# schematic_full.net
KiCad netlist of a schematic drawn in EAGLE
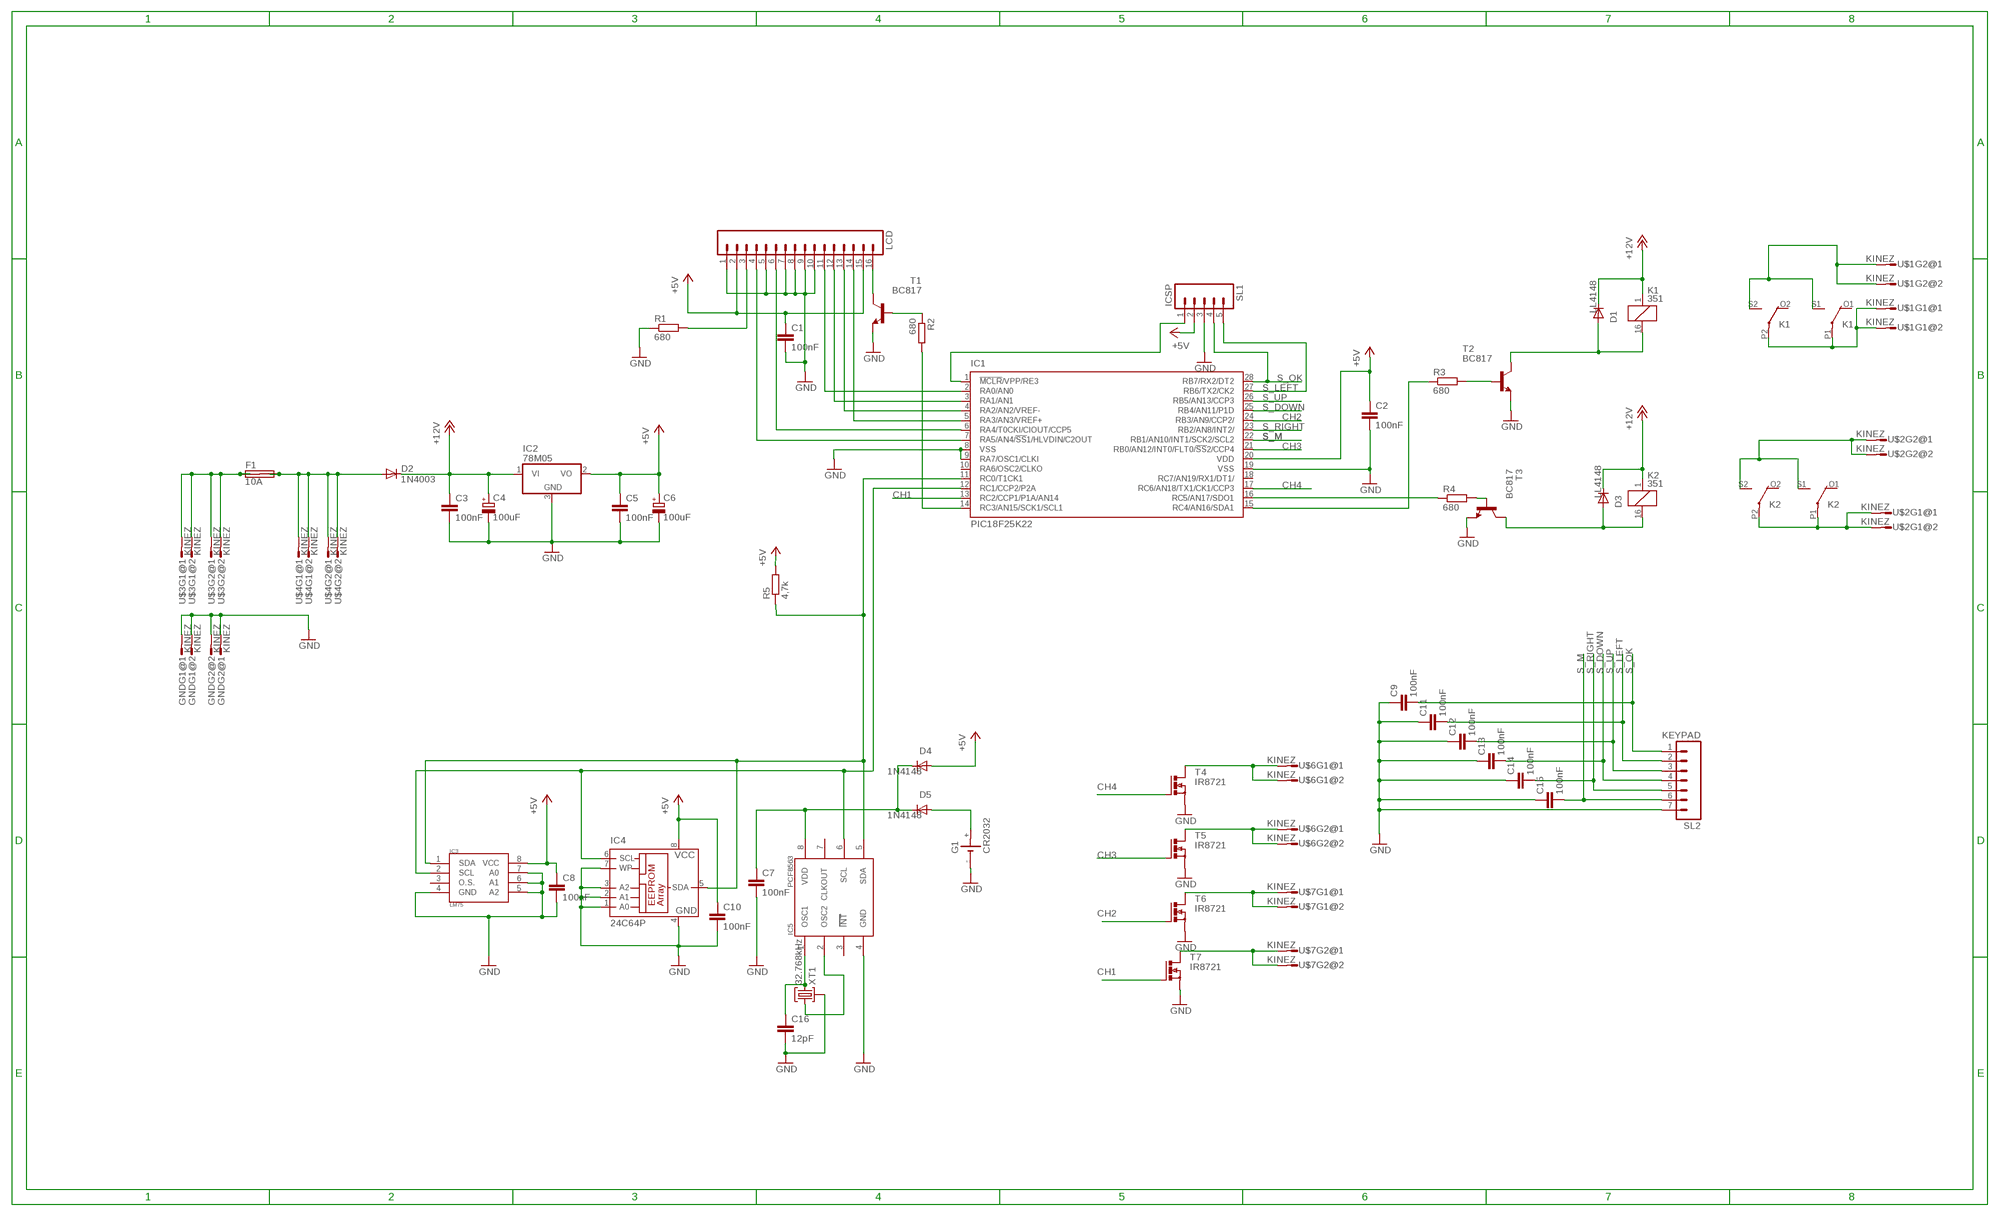
[diagram p0: schematic, sheet 1]

(export (version "E")
  (design (tool "Eeschema 10.0.6"))
  (components
    (comp (ref "C1")
      (value "100nF")
      (footprint "eagle-import:C0805K")
      (libsource (lib "eagle-import") (part "C-EUC0805K"))
    )
    (comp (ref "C2")
      (value "100nF")
      (footprint "eagle-import:C0805K")
      (libsource (lib "eagle-import") (part "C-EUC0805K"))
    )
    (comp (ref "C3")
      (value "100nF")
      (footprint "eagle-import:C0805K")
      (libsource (lib "eagle-import") (part "C-EUC0805K"))
    )
    (comp (ref "C4")
      (value "100uF")
      (footprint "eagle-import:E2,5-6E")
      (libsource (lib "eagle-import") (part "CPOL-EUE2,5-6E"))
    )
    (comp (ref "C5")
      (value "100nF")
      (footprint "eagle-import:C0805K")
      (libsource (lib "eagle-import") (part "C-EUC0805K"))
    )
    (comp (ref "C6")
      (value "100uF")
      (footprint "eagle-import:E2,5-6")
      (libsource (lib "eagle-import") (part "CPOL-EUE2.5-6"))
    )
    (comp (ref "C7")
      (value "100nF")
      (footprint "eagle-import:C0805K")
      (libsource (lib "eagle-import") (part "C-EUC0805K"))
    )
    (comp (ref "C8")
      (value "100nF")
      (footprint "eagle-import:C0805K")
      (libsource (lib "eagle-import") (part "C-EUC0805K"))
    )
    (comp (ref "C9")
      (value "100nF")
      (footprint "eagle-import:C0805K")
      (libsource (lib "eagle-import") (part "C-EUC0805K"))
    )
    (comp (ref "C10")
      (value "100nF")
      (footprint "eagle-import:C0805K")
      (libsource (lib "eagle-import") (part "C-EUC0805K"))
    )
    (comp (ref "C11")
      (value "100nF")
      (footprint "eagle-import:C0805K")
      (libsource (lib "eagle-import") (part "C-EUC0805K"))
    )
    (comp (ref "C12")
      (value "100nF")
      (footprint "eagle-import:C0805K")
      (libsource (lib "eagle-import") (part "C-EUC0805K"))
    )
    (comp (ref "C13")
      (value "100nF")
      (footprint "eagle-import:C0805K")
      (libsource (lib "eagle-import") (part "C-EUC0805K"))
    )
    (comp (ref "C14")
      (value "100nF")
      (footprint "eagle-import:C0805K")
      (libsource (lib "eagle-import") (part "C-EUC0805K"))
    )
    (comp (ref "C15")
      (value "100nF")
      (footprint "eagle-import:C0805K")
      (libsource (lib "eagle-import") (part "C-EUC0805K"))
    )
    (comp (ref "C16")
      (value "12pF")
      (footprint "eagle-import:C0805K")
      (libsource (lib "eagle-import") (part "C-EUC0805K"))
    )
    (comp (ref "D1")
      (value "LL4148")
      (footprint "eagle-import:DO214BA")
      (libsource (lib "eagle-import") (part "DIODE-DO214BA"))
    )
    (comp (ref "D2")
      (value "1N4003")
      (footprint "eagle-import:DO41-10")
      (libsource (lib "eagle-import") (part "1N4933"))
    )
    (comp (ref "D3")
      (value "LL4148")
      (footprint "eagle-import:DO214BA")
      (libsource (lib "eagle-import") (part "DIODE-DO214BA"))
    )
    (comp (ref "D4")
      (value "1N4148")
      (footprint "eagle-import:DO214BA")
      (libsource (lib "eagle-import") (part "DIODE-DO214BA"))
    )
    (comp (ref "D5")
      (value "1N4148")
      (footprint "eagle-import:DO214BA")
      (libsource (lib "eagle-import") (part "DIODE-DO214BA"))
    )
    (comp (ref "F1")
      (value "10A")
      (footprint "eagle-import:SHK20L")
      (libsource (lib "eagle-import") (part "SHK20L"))
    )
    (comp (ref "G1")
      (value "CR2032")
      (footprint "eagle-import:CR2032")
      (libsource (lib "eagle-import") (part "CR2032"))
    )
    (comp (ref "GND")
      (value "KINEZ")
      (footprint "eagle-import:KINEZ")
      (libsource (lib "eagle-import") (part "KINEZ"))
    )
    (comp (ref "IC1")
      (value "PIC18F25K22")
      (footprint "eagle-import:SSOP28")
      (libsource (lib "eagle-import") (part "PIC18F25K22/SS-E"))
    )
    (comp (ref "IC2")
      (value "78M05")
      (footprint "eagle-import:TO252")
      (libsource (lib "eagle-import") (part "78DT05"))
    )
    (comp (ref "IC3")
      (value "LM75")
      (footprint "eagle-import:SO08")
      (libsource (lib "eagle-import") (part "LM75"))
    )
    (comp (ref "IC4")
      (value "24C64P")
      (footprint "eagle-import:DIL8")
      (libsource (lib "eagle-import") (part "24PC64"))
    )
    (comp (ref "IC5")
      (value "PCF8563")
      (footprint "eagle-import:SO08")
      (libsource (lib "eagle-import") (part "PCF8563"))
    )
    (comp (ref "K1")
      (value "351")
      (footprint "eagle-import:351")
      (libsource (lib "eagle-import") (part "351"))
    )
    (comp (ref "K2")
      (value "351")
      (footprint "eagle-import:351")
      (libsource (lib "eagle-import") (part "351"))
    )
    (comp (ref "LCD")
      (value "M16")
      (footprint "eagle-import:16P")
      (libsource (lib "eagle-import") (part "M16"))
    )
    (comp (ref "R1")
      (value "680")
      (footprint "eagle-import:M0805")
      (libsource (lib "eagle-import") (part "R-EU_M0805"))
    )
    (comp (ref "R2")
      (value "680")
      (footprint "eagle-import:M0805")
      (libsource (lib "eagle-import") (part "R-EU_M0805"))
    )
    (comp (ref "R3")
      (value "680")
      (footprint "eagle-import:M0805")
      (libsource (lib "eagle-import") (part "R-EU_M0805"))
    )
    (comp (ref "R4")
      (value "680")
      (footprint "eagle-import:M0805")
      (libsource (lib "eagle-import") (part "R-EU_M0805"))
    )
    (comp (ref "R5")
      (value "4,7k")
      (footprint "eagle-import:M0805")
      (libsource (lib "eagle-import") (part "R-EU_M0805"))
    )
    (comp (ref "SL1")
      (value "ICSP")
      (footprint "eagle-import:05P")
      (libsource (lib "eagle-import") (part "M05"))
    )
    (comp (ref "SL2")
      (value "KEYPAD")
      (footprint "eagle-import:07PA")
      (libsource (lib "eagle-import") (part "MA07"))
    )
    (comp (ref "T1")
      (value "BC817")
      (footprint "eagle-import:SOT23-BEC")
      (libsource (lib "eagle-import") (part "BC817SMD-40"))
    )
    (comp (ref "T2")
      (value "BC817")
      (footprint "eagle-import:SOT23-BEC")
      (libsource (lib "eagle-import") (part "BC817SMD-40"))
    )
    (comp (ref "T3")
      (value "BC817")
      (footprint "eagle-import:SOT23-BEC")
      (libsource (lib "eagle-import") (part "BC817SMD-40"))
    )
    (comp (ref "T4")
      (value "IR8721")
      (footprint "eagle-import:TO252")
      (libsource (lib "eagle-import") (part "IRLR120N"))
    )
    (comp (ref "T5")
      (value "IR8721")
      (footprint "eagle-import:TO252")
      (libsource (lib "eagle-import") (part "IRLR120N"))
    )
    (comp (ref "T6")
      (value "IR8721")
      (footprint "eagle-import:TO252")
      (libsource (lib "eagle-import") (part "IRLR120N"))
    )
    (comp (ref "T7")
      (value "IR8721")
      (footprint "eagle-import:TO252")
      (libsource (lib "eagle-import") (part "IRLR120N"))
    )
    (comp (ref "U$1")
      (value "KINEZ")
      (footprint "eagle-import:KINEZ")
      (libsource (lib "eagle-import") (part "KINEZ"))
    )
    (comp (ref "U$2")
      (value "KINEZ")
      (footprint "eagle-import:KINEZ")
      (libsource (lib "eagle-import") (part "KINEZ"))
    )
    (comp (ref "U$3")
      (value "KINEZ")
      (footprint "eagle-import:KINEZ")
      (libsource (lib "eagle-import") (part "KINEZ"))
    )
    (comp (ref "U$4")
      (value "KINEZ")
      (footprint "eagle-import:KINEZ")
      (libsource (lib "eagle-import") (part "KINEZ"))
    )
    (comp (ref "U$6")
      (value "KINEZ")
      (footprint "eagle-import:KINEZ")
      (libsource (lib "eagle-import") (part "KINEZ"))
    )
    (comp (ref "U$7")
      (value "KINEZ")
      (footprint "eagle-import:KINEZ")
      (libsource (lib "eagle-import") (part "KINEZ"))
    )
    (comp (ref "XT1")
      (value "32.768kHz")
      (footprint "eagle-import:XTMINI")
      (libsource (lib "eagle-import") (part "XTMINI"))
    )
  )
  (nets
    (net (code "1") (name "+5V") (class "Default")
      (node (ref "C1") (pin "1") (pinfunction "1_1") (pintype "passive"))
      (node (ref "C10") (pin "1") (pinfunction "1_1") (pintype "passive"))
      (node (ref "C2") (pin "1") (pinfunction "1_1") (pintype "passive"))
      (node (ref "C5") (pin "1") (pinfunction "1_1") (pintype "passive"))
      (node (ref "C6") (pin "+") (pinfunction "+_+") (pintype "passive"))
      (node (ref "C8") (pin "1") (pinfunction "1_1") (pintype "passive"))
      (node (ref "D4") (pin "A") (pinfunction "A_A") (pintype "passive"))
      (node (ref "IC1") (pin "20") (pinfunction "VDD_20") (pintype "power_in"))
      (node (ref "IC2") (pin "2") (pinfunction "VO_2") (pintype "passive"))
      (node (ref "IC3") (pin "8") (pinfunction "VCC_8") (pintype "bidirectional"))
      (node (ref "IC4") (pin "8") (pinfunction "VCC_8") (pintype "power_in"))
      (node (ref "LCD") (pin "15") (pinfunction "15_15") (pintype "passive"))
      (node (ref "LCD") (pin "2") (pinfunction "2_2") (pintype "passive"))
      (node (ref "R5") (pin "2") (pinfunction "2_2") (pintype "passive"))
      (node (ref "SL1") (pin "2") (pinfunction "2_2") (pintype "passive"))
    )
    (net (code "2") (name "+12V") (class "Default")
      (node (ref "C3") (pin "1") (pinfunction "1_1") (pintype "passive"))
      (node (ref "C4") (pin "+") (pinfunction "+_+") (pintype "passive"))
      (node (ref "D1") (pin "C") (pinfunction "C_C") (pintype "passive"))
      (node (ref "D2") (pin "C") (pinfunction "C_C") (pintype "passive"))
      (node (ref "D3") (pin "C") (pinfunction "C_C") (pintype "passive"))
      (node (ref "IC2") (pin "1") (pinfunction "VI_1") (pintype "input"))
      (node (ref "K1") (pin "1") (pinfunction "1_1") (pintype "passive"))
      (node (ref "K2") (pin "1") (pinfunction "1_1") (pintype "passive"))
    )
    (net (code "3") (name "/CH1") (class "Default")
      (node (ref "IC1") (pin "13") (pinfunction "RC2/CCP1/P1A/AN14_13") (pintype "bidirectional"))
      (node (ref "T7") (pin "1") (pinfunction "G_1") (pintype "passive"))
    )
    (net (code "4") (name "/CH2") (class "Default")
      (node (ref "IC1") (pin "24") (pinfunction "RB3/AN9/CCP2/_24") (pintype "bidirectional"))
      (node (ref "T6") (pin "1") (pinfunction "G_1") (pintype "passive"))
    )
    (net (code "5") (name "/CH3") (class "Default")
      (node (ref "IC1") (pin "21") (pinfunction "RB0/AN12/INT0/FLT0/~{SS}2/CCP4_21") (pintype "bidirectional"))
      (node (ref "T5") (pin "1") (pinfunction "G_1") (pintype "passive"))
    )
    (net (code "6") (name "/CH4") (class "Default")
      (node (ref "IC1") (pin "17") (pinfunction "RC6/AN18/TX1/CK1/CCP3_17") (pintype "bidirectional"))
      (node (ref "T4") (pin "1") (pinfunction "G_1") (pintype "passive"))
    )
    (net (code "7") (name "/S_DOWN") (class "Default")
      (node (ref "C13") (pin "2") (pinfunction "2_2") (pintype "passive"))
      (node (ref "IC1") (pin "25") (pinfunction "RB4/AN11/P1D_25") (pintype "bidirectional"))
      (node (ref "SL2") (pin "4") (pinfunction "4_4") (pintype "passive"))
    )
    (net (code "8") (name "/S_LEFT") (class "Default")
      (node (ref "C11") (pin "2") (pinfunction "2_2") (pintype "passive"))
      (node (ref "IC1") (pin "27") (pinfunction "RB6/TX2/CK2_27") (pintype "bidirectional"))
      (node (ref "SL1") (pin "5") (pinfunction "5_5") (pintype "passive"))
      (node (ref "SL2") (pin "2") (pinfunction "2_2") (pintype "passive"))
    )
    (net (code "9") (name "/S_M") (class "Default")
      (node (ref "C15") (pin "2") (pinfunction "2_2") (pintype "passive"))
      (node (ref "IC1") (pin "22") (pinfunction "RB1/AN10/INT1/SCK2/SCL2_22") (pintype "bidirectional"))
      (node (ref "SL2") (pin "6") (pinfunction "6_6") (pintype "passive"))
    )
    (net (code "10") (name "/S_OK") (class "Default")
      (node (ref "C9") (pin "2") (pinfunction "2_2") (pintype "passive"))
      (node (ref "IC1") (pin "28") (pinfunction "RB7/RX2/DT2_28") (pintype "bidirectional"))
      (node (ref "SL1") (pin "4") (pinfunction "4_4") (pintype "passive"))
      (node (ref "SL2") (pin "1") (pinfunction "1_1") (pintype "passive"))
    )
    (net (code "11") (name "/S_RIGHT") (class "Default")
      (node (ref "C14") (pin "2") (pinfunction "2_2") (pintype "passive"))
      (node (ref "IC1") (pin "23") (pinfunction "RB2/AN8/INT2/_23") (pintype "bidirectional"))
      (node (ref "SL2") (pin "5") (pinfunction "5_5") (pintype "passive"))
    )
    (net (code "12") (name "/S_UP") (class "Default")
      (node (ref "C12") (pin "2") (pinfunction "2_2") (pintype "passive"))
      (node (ref "IC1") (pin "26") (pinfunction "RB5/AN13/CCP3_26") (pintype "bidirectional"))
      (node (ref "SL2") (pin "3") (pinfunction "3_3") (pintype "passive"))
    )
    (net (code "13") (name "GND") (class "Default")
      (node (ref "C1") (pin "2") (pinfunction "2_2") (pintype "passive"))
      (node (ref "C10") (pin "2") (pinfunction "2_2") (pintype "passive"))
      (node (ref "C11") (pin "1") (pinfunction "1_1") (pintype "passive"))
      (node (ref "C12") (pin "1") (pinfunction "1_1") (pintype "passive"))
      (node (ref "C13") (pin "1") (pinfunction "1_1") (pintype "passive"))
      (node (ref "C14") (pin "1") (pinfunction "1_1") (pintype "passive"))
      (node (ref "C15") (pin "1") (pinfunction "1_1") (pintype "passive"))
      (node (ref "C16") (pin "2") (pinfunction "2_2") (pintype "passive"))
      (node (ref "C2") (pin "2") (pinfunction "2_2") (pintype "passive"))
      (node (ref "C3") (pin "2") (pinfunction "2_2") (pintype "passive"))
      (node (ref "C4") (pin "-") (pinfunction "-_-") (pintype "passive"))
      (node (ref "C5") (pin "2") (pinfunction "2_2") (pintype "passive"))
      (node (ref "C6") (pin "-") (pinfunction "-_-") (pintype "passive"))
      (node (ref "C7") (pin "2") (pinfunction "2_2") (pintype "passive"))
      (node (ref "C8") (pin "2") (pinfunction "2_2") (pintype "passive"))
      (node (ref "C9") (pin "1") (pinfunction "1_1") (pintype "passive"))
      (node (ref "G1") (pin "-") (pinfunction "-_-") (pintype "passive"))
      (node (ref "GND") (pin "1") (pinfunction "S_1") (pintype "passive"))
      (node (ref "GND") (pin "2") (pinfunction "S_2") (pintype "passive"))
      (node (ref "GND") (pin "3") (pinfunction "S_3") (pintype "passive"))
      (node (ref "GND") (pin "4") (pinfunction "S_4") (pintype "passive"))
      (node (ref "IC1") (pin "19") (pinfunction "VSS_19") (pintype "power_in"))
      (node (ref "IC1") (pin "8") (pinfunction "VSS_8") (pintype "power_in"))
      (node (ref "IC1") (pin "9") (pinfunction "RA7/OSC1/CLKI_9") (pintype "input"))
      (node (ref "IC2") (pin "3") (pinfunction "GND_3") (pintype "passive"))
      (node (ref "IC3") (pin "4") (pinfunction "GND_4") (pintype "bidirectional"))
      (node (ref "IC3") (pin "5") (pinfunction "A2_5") (pintype "bidirectional"))
      (node (ref "IC3") (pin "6") (pinfunction "A1_6") (pintype "bidirectional"))
      (node (ref "IC3") (pin "7") (pinfunction "A0_7") (pintype "bidirectional"))
      (node (ref "IC4") (pin "1") (pinfunction "A0_1") (pintype "input"))
      (node (ref "IC4") (pin "2") (pinfunction "A1_2") (pintype "input"))
      (node (ref "IC4") (pin "3") (pinfunction "A2_3") (pintype "input"))
      (node (ref "IC4") (pin "4") (pinfunction "GND_4") (pintype "power_in"))
      (node (ref "IC4") (pin "7") (pinfunction "WP_7") (pintype "input"))
      (node (ref "IC5") (pin "4") (pinfunction "GND_4") (pintype "bidirectional"))
      (node (ref "LCD") (pin "1") (pinfunction "1_1") (pintype "passive"))
      (node (ref "LCD") (pin "10") (pinfunction "10_10") (pintype "passive"))
      (node (ref "LCD") (pin "5") (pinfunction "5_5") (pintype "passive"))
      (node (ref "LCD") (pin "7") (pinfunction "7_7") (pintype "passive"))
      (node (ref "LCD") (pin "8") (pinfunction "8_8") (pintype "passive"))
      (node (ref "LCD") (pin "9") (pinfunction "9_9") (pintype "passive"))
      (node (ref "R1") (pin "1") (pinfunction "1_1") (pintype "passive"))
      (node (ref "SL1") (pin "3") (pinfunction "3_3") (pintype "passive"))
      (node (ref "SL2") (pin "7") (pinfunction "7_7") (pintype "passive"))
      (node (ref "T1") (pin "E") (pinfunction "E_E") (pintype "passive"))
      (node (ref "T2") (pin "E") (pinfunction "E_E") (pintype "passive"))
      (node (ref "T3") (pin "E") (pinfunction "E_E") (pintype "passive"))
      (node (ref "T4") (pin "3") (pinfunction "S_3") (pintype "passive"))
      (node (ref "T5") (pin "3") (pinfunction "S_3") (pintype "passive"))
      (node (ref "T6") (pin "3") (pinfunction "S_3") (pintype "passive"))
      (node (ref "T7") (pin "3") (pinfunction "S_3") (pintype "passive"))
      (node (ref "XT1") (pin "P$3") (pinfunction "3_P$3") (pintype "passive"))
    )
    (net (code "14") (name "Net-(D5-PadA)") (class "Default")
      (node (ref "D5") (pin "A") (pinfunction "A_A") (pintype "passive"))
      (node (ref "G1") (pin "+") (pinfunction "+_+") (pintype "passive"))
    )
    (net (code "15") (name "Net-(IC1-RA0{slash}AN0)") (class "Default")
      (node (ref "IC1") (pin "2") (pinfunction "RA0/AN0_2") (pintype "bidirectional"))
      (node (ref "LCD") (pin "11") (pinfunction "11_11") (pintype "passive"))
    )
    (net (code "16") (name "Net-(IC1-RA1{slash}AN1)") (class "Default")
      (node (ref "IC1") (pin "3") (pinfunction "RA1/AN1_3") (pintype "bidirectional"))
      (node (ref "LCD") (pin "12") (pinfunction "12_12") (pintype "passive"))
    )
    (net (code "17") (name "Net-(IC1-RA2{slash}AN2{slash}VREF-)") (class "Default")
      (node (ref "IC1") (pin "4") (pinfunction "RA2/AN2/VREF-_4") (pintype "bidirectional"))
      (node (ref "LCD") (pin "13") (pinfunction "13_13") (pintype "passive"))
    )
    (net (code "18") (name "Net-(IC1-RA3{slash}AN3{slash}VREF+)") (class "Default")
      (node (ref "IC1") (pin "5") (pinfunction "RA3/AN3/VREF+_5") (pintype "bidirectional"))
      (node (ref "LCD") (pin "14") (pinfunction "14_14") (pintype "passive"))
    )
    (net (code "19") (name "Net-(IC1-RA4{slash}T0CKI{slash}CIOUT{slash}CCP5)") (class "Default")
      (node (ref "IC1") (pin "6") (pinfunction "RA4/T0CKI/CIOUT/CCP5_6") (pintype "bidirectional"))
      (node (ref "LCD") (pin "6") (pinfunction "6_6") (pintype "passive"))
    )
    (net (code "20") (name "Net-(IC1-RA5{slash}AN4{slash}~{SS}1{slash}HLVDIN{slash}C2OUT)") (class "Default")
      (node (ref "IC1") (pin "7") (pinfunction "RA5/AN4/~{SS}1/HLVDIN/C2OUT_7") (pintype "bidirectional"))
      (node (ref "LCD") (pin "4") (pinfunction "4_4") (pintype "passive"))
    )
    (net (code "21") (name "Net-(IC1-RC0{slash}T1CK1)") (class "Default")
      (node (ref "IC1") (pin "11") (pinfunction "RC0/T1CK1_11") (pintype "bidirectional"))
      (node (ref "IC3") (pin "1") (pinfunction "SDA_1") (pintype "bidirectional"))
      (node (ref "IC4") (pin "5") (pinfunction "SDA_5") (pintype "bidirectional"))
      (node (ref "IC5") (pin "5") (pinfunction "SDA_5") (pintype "bidirectional"))
      (node (ref "R5") (pin "1") (pinfunction "1_1") (pintype "passive"))
    )
    (net (code "22") (name "Net-(IC1-RC1{slash}CCP2{slash}P2A)") (class "Default")
      (node (ref "IC1") (pin "12") (pinfunction "RC1/CCP2/P2A_12") (pintype "bidirectional"))
      (node (ref "IC3") (pin "2") (pinfunction "SCL_2") (pintype "bidirectional"))
      (node (ref "IC4") (pin "6") (pinfunction "SCL_6") (pintype "input"))
      (node (ref "IC5") (pin "6") (pinfunction "SCL_6") (pintype "bidirectional"))
    )
    (net (code "23") (name "Net-(IC1-RC3{slash}AN15{slash}SCK1{slash}SCL1)") (class "Default")
      (node (ref "IC1") (pin "14") (pinfunction "RC3/AN15/SCK1/SCL1_14") (pintype "bidirectional"))
      (node (ref "R2") (pin "2") (pinfunction "2_2") (pintype "passive"))
    )
    (net (code "24") (name "Net-(IC1-RC4{slash}AN16{slash}SDA1)") (class "Default")
      (node (ref "IC1") (pin "15") (pinfunction "RC4/AN16/SDA1_15") (pintype "bidirectional"))
      (node (ref "R3") (pin "1") (pinfunction "1_1") (pintype "passive"))
    )
    (net (code "25") (name "Net-(IC1-RC5{slash}AN17{slash}SDO1)") (class "Default")
      (node (ref "IC1") (pin "16") (pinfunction "RC5/AN17/SDO1_16") (pintype "bidirectional"))
      (node (ref "R4") (pin "1") (pinfunction "1_1") (pintype "passive"))
    )
    (net (code "26") (name "Net-(IC1-~{MCLR}{slash}VPP{slash}RE3)") (class "Default")
      (node (ref "IC1") (pin "1") (pinfunction "~{MCLR}/VPP/RE3_1") (pintype "input"))
      (node (ref "SL1") (pin "1") (pinfunction "1_1") (pintype "passive"))
    )
    (net (code "27") (name "Net-(IC5-OSC1)") (class "Default")
      (node (ref "C16") (pin "1") (pinfunction "1_1") (pintype "passive"))
      (node (ref "IC5") (pin "1") (pinfunction "OSC1_1") (pintype "bidirectional"))
      (node (ref "XT1") (pin "P$2") (pinfunction "2_P$2") (pintype "passive"))
    )
    (net (code "28") (name "Net-(IC5-OSC2)") (class "Default")
      (node (ref "IC5") (pin "2") (pinfunction "OSC2_2") (pintype "bidirectional"))
      (node (ref "XT1") (pin "P$1") (pinfunction "1_P$1") (pintype "passive"))
    )
    (net (code "29") (name "Net-(IC5-VDD)") (class "Default")
      (node (ref "C7") (pin "1") (pinfunction "1_1") (pintype "passive"))
      (node (ref "D4") (pin "C") (pinfunction "C_C") (pintype "passive"))
      (node (ref "D5") (pin "C") (pinfunction "C_C") (pintype "passive"))
      (node (ref "IC5") (pin "8") (pinfunction "VDD_8") (pintype "bidirectional"))
    )
    (net (code "30") (name "Net-(K1A-2)") (class "Default")
      (node (ref "D1") (pin "A") (pinfunction "A_A") (pintype "passive"))
      (node (ref "K1") (pin "16") (pinfunction "2_16") (pintype "passive"))
      (node (ref "T2") (pin "C") (pinfunction "C_C") (pintype "passive"))
    )
    (net (code "31") (name "Net-(K1B-P)") (class "Default")
      (node (ref "K1") (pin "P1") (pinfunction "P_P1") (pintype "passive"))
      (node (ref "K1") (pin "P2") (pinfunction "P_P2") (pintype "passive"))
      (node (ref "U$1") (pin "1") (pinfunction "S_1") (pintype "passive"))
      (node (ref "U$1") (pin "2") (pinfunction "S_2") (pintype "passive"))
    )
    (net (code "32") (name "Net-(K1B-S)") (class "Default")
      (node (ref "K1") (pin "S1") (pinfunction "S_S1") (pintype "passive"))
      (node (ref "K1") (pin "S2") (pinfunction "S_S2") (pintype "passive"))
      (node (ref "U$1") (pin "3") (pinfunction "S_3") (pintype "passive"))
      (node (ref "U$1") (pin "4") (pinfunction "S_4") (pintype "passive"))
    )
    (net (code "33") (name "Net-(K2A-2)") (class "Default")
      (node (ref "D3") (pin "A") (pinfunction "A_A") (pintype "passive"))
      (node (ref "K2") (pin "16") (pinfunction "2_16") (pintype "passive"))
      (node (ref "T3") (pin "C") (pinfunction "C_C") (pintype "passive"))
    )
    (net (code "34") (name "Net-(K2B-P)") (class "Default")
      (node (ref "K2") (pin "P1") (pinfunction "P_P1") (pintype "passive"))
      (node (ref "K2") (pin "P2") (pinfunction "P_P2") (pintype "passive"))
      (node (ref "U$2") (pin "1") (pinfunction "S_1") (pintype "passive"))
      (node (ref "U$2") (pin "2") (pinfunction "S_2") (pintype "passive"))
    )
    (net (code "35") (name "Net-(K2B-S)") (class "Default")
      (node (ref "K2") (pin "S1") (pinfunction "S_S1") (pintype "passive"))
      (node (ref "K2") (pin "S2") (pinfunction "S_S2") (pintype "passive"))
      (node (ref "U$2") (pin "3") (pinfunction "S_3") (pintype "passive"))
      (node (ref "U$2") (pin "4") (pinfunction "S_4") (pintype "passive"))
    )
    (net (code "36") (name "Net-(LCD-Pad3)") (class "Default")
      (node (ref "LCD") (pin "3") (pinfunction "3_3") (pintype "passive"))
      (node (ref "R1") (pin "2") (pinfunction "2_2") (pintype "passive"))
    )
    (net (code "37") (name "Net-(LCD-Pad16)") (class "Default")
      (node (ref "LCD") (pin "16") (pinfunction "16_16") (pintype "passive"))
      (node (ref "T1") (pin "C") (pinfunction "C_C") (pintype "passive"))
    )
    (net (code "38") (name "Net-(R2-Pad1)") (class "Default")
      (node (ref "R2") (pin "1") (pinfunction "1_1") (pintype "passive"))
      (node (ref "T1") (pin "B") (pinfunction "B_B") (pintype "passive"))
    )
    (net (code "39") (name "Net-(R3-Pad2)") (class "Default")
      (node (ref "R3") (pin "2") (pinfunction "2_2") (pintype "passive"))
      (node (ref "T2") (pin "B") (pinfunction "B_B") (pintype "passive"))
    )
    (net (code "40") (name "Net-(R4-Pad2)") (class "Default")
      (node (ref "R4") (pin "2") (pinfunction "2_2") (pintype "passive"))
      (node (ref "T3") (pin "B") (pinfunction "B_B") (pintype "passive"))
    )
    (net (code "41") (name "Net-(T4-D)") (class "Default")
      (node (ref "T4") (pin "2") (pinfunction "D_2") (pintype "passive"))
      (node (ref "U$6") (pin "1") (pinfunction "S_1") (pintype "passive"))
      (node (ref "U$6") (pin "2") (pinfunction "S_2") (pintype "passive"))
    )
    (net (code "42") (name "Net-(T5-D)") (class "Default")
      (node (ref "T5") (pin "2") (pinfunction "D_2") (pintype "passive"))
      (node (ref "U$6") (pin "3") (pinfunction "S_3") (pintype "passive"))
      (node (ref "U$6") (pin "4") (pinfunction "S_4") (pintype "passive"))
    )
    (net (code "43") (name "Net-(T6-D)") (class "Default")
      (node (ref "T6") (pin "2") (pinfunction "D_2") (pintype "passive"))
      (node (ref "U$7") (pin "1") (pinfunction "S_1") (pintype "passive"))
      (node (ref "U$7") (pin "2") (pinfunction "S_2") (pintype "passive"))
    )
    (net (code "44") (name "Net-(T7-D)") (class "Default")
      (node (ref "T7") (pin "2") (pinfunction "D_2") (pintype "passive"))
      (node (ref "U$7") (pin "3") (pinfunction "S_3") (pintype "passive"))
      (node (ref "U$7") (pin "4") (pinfunction "S_4") (pintype "passive"))
    )
    (net (code "45") (name "Net-(U$3A-S)") (class "Default")
      (node (ref "F1") (pin "1A") (pinfunction "1A_1A") (pintype "passive"))
      (node (ref "F1") (pin "1B") (pinfunction "1B_1B") (pintype "passive"))
      (node (ref "U$3") (pin "1") (pinfunction "S_1") (pintype "passive"))
      (node (ref "U$3") (pin "2") (pinfunction "S_2") (pintype "passive"))
      (node (ref "U$3") (pin "3") (pinfunction "S_3") (pintype "passive"))
      (node (ref "U$3") (pin "4") (pinfunction "S_4") (pintype "passive"))
    )
    (net (code "46") (name "Net-(U$4A-S)") (class "Default")
      (node (ref "D2") (pin "A") (pinfunction "A_A") (pintype "passive"))
      (node (ref "F1") (pin "2A") (pinfunction "2A_2A") (pintype "passive"))
      (node (ref "F1") (pin "2B") (pinfunction "2B_2B") (pintype "passive"))
      (node (ref "U$4") (pin "1") (pinfunction "S_1") (pintype "passive"))
      (node (ref "U$4") (pin "2") (pinfunction "S_2") (pintype "passive"))
      (node (ref "U$4") (pin "3") (pinfunction "S_3") (pintype "passive"))
      (node (ref "U$4") (pin "4") (pinfunction "S_4") (pintype "passive"))
    )
    (net (code "47") (name "unconnected-(IC1-RA6{slash}OSC2{slash}CLKO-Pad10)") (class "Default")
      (node (ref "IC1") (pin "10") (pinfunction "RA6/OSC2/CLKO_10") (pintype "output"))
    )
    (net (code "48") (name "unconnected-(IC1-RC7{slash}AN19{slash}RX1{slash}DT1{slash}-Pad18)") (class "Default")
      (node (ref "IC1") (pin "18") (pinfunction "RC7/AN19/RX1/DT1/_18") (pintype "bidirectional"))
    )
    (net (code "49") (name "unconnected-(IC3-O.S.-Pad3)") (class "Default")
      (node (ref "IC3") (pin "3") (pinfunction "O.S._3") (pintype "bidirectional"))
    )
    (net (code "50") (name "unconnected-(IC5-CLKOUT-Pad7)") (class "Default")
      (node (ref "IC5") (pin "7") (pinfunction "CLKOUT_7") (pintype "bidirectional"))
    )
    (net (code "51") (name "unconnected-(IC5-INT-Pad3)") (class "Default")
      (node (ref "IC5") (pin "3") (pinfunction "INT_3") (pintype "bidirectional"))
    )
    (net (code "52") (name "unconnected-(K1B-O-PadO1)") (class "Default")
      (node (ref "K1") (pin "O1") (pinfunction "O_O1") (pintype "passive"))
    )
    (net (code "53") (name "unconnected-(K1C-O-PadO2)") (class "Default")
      (node (ref "K1") (pin "O2") (pinfunction "O_O2") (pintype "passive"))
    )
    (net (code "54") (name "unconnected-(K2B-O-PadO1)") (class "Default")
      (node (ref "K2") (pin "O1") (pinfunction "O_O1") (pintype "passive"))
    )
    (net (code "55") (name "unconnected-(K2C-O-PadO2)") (class "Default")
      (node (ref "K2") (pin "O2") (pinfunction "O_O2") (pintype "passive"))
    )
  )
)
